# ROBO_HAND_SCH.net
KiCad netlist of a schematic drawn in Altium Designer
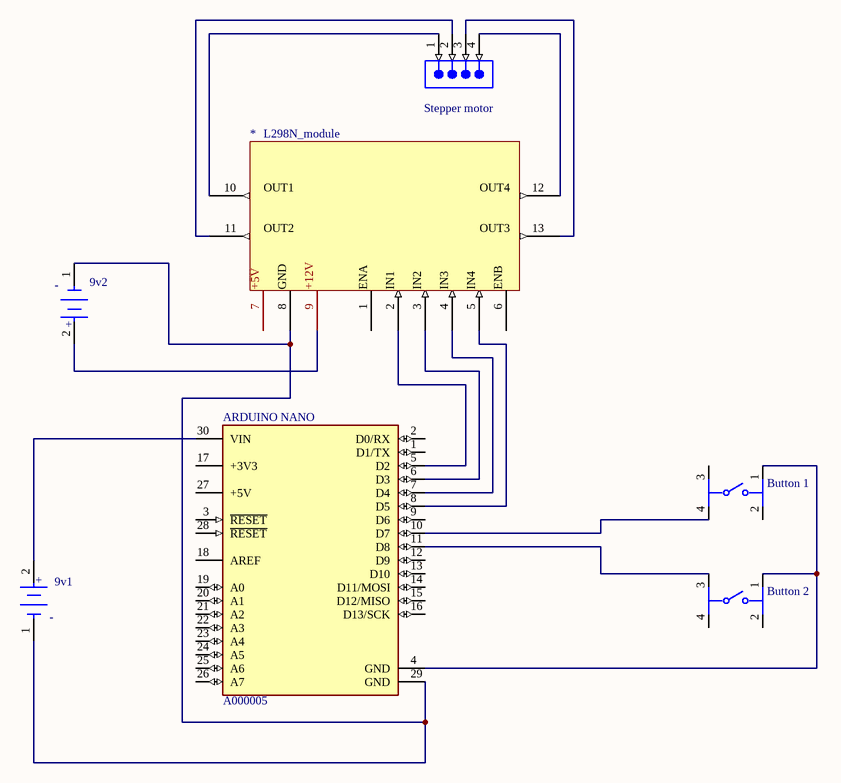
[diagram p0: ROBO HAND SCH.SchDoc]

(export (version "E")
  (design (tool "Eeschema 10.0.6"))
  (components
    (comp (ref "*") (value "L298N_module") (libsource (lib "L298N_module") (part "L298N_module")))
    (comp (ref "9v1")
      (value "BH9VPC")
      (footprint "FP-BH9VPC-MFG")
      (description "Battery Holder (Open) 9V 1 Cell PC Pin")
      (fields (field (name "OCTOPART") "https://octopart.com/bh9vpc-memory+protection+devices-22788154"))
      (libsource (lib "Altium Content Vault") (part "60d3b5b901a8747834971d0eb8cf3fd"))
    )
    (comp (ref "9v2")
      (value "BH9VPC")
      (footprint "FP-BH9VPC-MFG")
      (description "Battery Holder (Open) 9V 1 Cell PC Pin")
      (fields (field (name "OCTOPART") "https://octopart.com/bh9vpc-memory+protection+devices-22788154"))
      (libsource (lib "Altium Content Vault") (part "60d3b5b901a8747834971d0eb8cf3fd"))
    )
    (comp (ref "ARDUINO NANO")
      (value "A000005")
      (footprint "FP-A000005-MFG")
      (description "ARDUINO NANO ATMEGA328 EVAL BRD")
      (libsource (lib "Altium Content Vault") (part "d190c066e99afd1c6882cf92e11b2cc"))
    )
    (comp (ref "Button 1")
      (value "PTS645SM43SMTR92LFS")
      (footprint "FP-PTS645SM43SMTR92LFS-MFG")
      (description "SWITCH TACTILE SPST-NO 0.05A 12V")
      (libsource (lib "Altium Content Vault") (part "1adf0dd01260c80cf25a44bfd6b99ba"))
    )
    (comp (ref "Button 2")
      (value "PTS645SM43SMTR92LFS")
      (footprint "FP-PTS645SM43SMTR92LFS-MFG")
      (description "SWITCH TACTILE SPST-NO 0.05A 12V")
      (libsource (lib "Altium Content Vault") (part "1adf0dd01260c80cf25a44bfd6b99ba"))
    )
    (comp (ref "Stepper motor")
      (value "TSM-104-01-L-SH")
      (footprint "SMTC-TSM-104-01-X-SH")
      (fields (field (name "MANUFACTURER") "Samtec"))
      (libsource (lib "Altium Content Vault") (part "SMTC-TSM-104-01-X-SH"))
    )
  )
  (nets
    (net (code "1") (name "Net-(*-+12V)") (class "Default")
      (node (ref "*") (pin "9") (pinfunction "+12V_9") (pintype "power_in"))
      (node (ref "9v2") (pin "2") (pinfunction "A_2") (pintype "passive"))
    )
    (net (code "2") (name "Net-(*-GND)") (class "Default")
      (node (ref "*") (pin "8") (pinfunction "GND_8") (pintype "power_in"))
      (node (ref "9v1") (pin "1") (pinfunction "C_1") (pintype "passive"))
      (node (ref "9v2") (pin "1") (pinfunction "C_1") (pintype "passive"))
      (node (ref "ARDUINO NANO") (pin "29") (pinfunction "GND_29") (pintype "power_in"))
    )
    (net (code "3") (name "Net-(*-IN1)") (class "Default")
      (node (ref "*") (pin "2") (pinfunction "IN1_2") (pintype "input"))
      (node (ref "ARDUINO NANO") (pin "5") (pinfunction "D2_5") (pintype "bidirectional"))
    )
    (net (code "4") (name "Net-(*-IN2)") (class "Default")
      (node (ref "*") (pin "3") (pinfunction "IN2_3") (pintype "input"))
      (node (ref "ARDUINO NANO") (pin "6") (pinfunction "D3_6") (pintype "bidirectional"))
    )
    (net (code "5") (name "Net-(*-IN3)") (class "Default")
      (node (ref "*") (pin "4") (pinfunction "IN3_4") (pintype "input"))
      (node (ref "ARDUINO NANO") (pin "7") (pinfunction "D4_7") (pintype "bidirectional"))
    )
    (net (code "6") (name "Net-(*-IN4)") (class "Default")
      (node (ref "*") (pin "5") (pinfunction "IN4_5") (pintype "input"))
      (node (ref "ARDUINO NANO") (pin "8") (pinfunction "D5_8") (pintype "bidirectional"))
    )
    (net (code "7") (name "Net-(*-OUT1)") (class "Default")
      (node (ref "*") (pin "10") (pinfunction "OUT1_10") (pintype "output"))
      (node (ref "Stepper motor") (pin "1") (pinfunction "A+_1") (pintype "input"))
    )
    (net (code "8") (name "Net-(*-OUT2)") (class "Default")
      (node (ref "*") (pin "11") (pinfunction "OUT2_11") (pintype "output"))
      (node (ref "Stepper motor") (pin "2") (pinfunction "A-_2") (pintype "input"))
    )
    (net (code "9") (name "Net-(*-OUT3)") (class "Default")
      (node (ref "*") (pin "13") (pinfunction "OUT3_13") (pintype "output"))
      (node (ref "Stepper motor") (pin "3") (pinfunction "B+_3") (pintype "input"))
    )
    (net (code "10") (name "Net-(*-OUT4)") (class "Default")
      (node (ref "*") (pin "12") (pinfunction "OUT4_12") (pintype "output"))
      (node (ref "Stepper motor") (pin "4") (pinfunction "B-_4") (pintype "input"))
    )
    (net (code "11") (name "Net-(9v1-A)") (class "Default")
      (node (ref "9v1") (pin "2") (pinfunction "A_2") (pintype "passive"))
      (node (ref "ARDUINO NANO") (pin "30") (pinfunction "VIN_30") (pintype "power_in"))
    )
    (net (code "12") (name "Net-(ARDUINO NANO-D7)") (class "Default")
      (node (ref "ARDUINO NANO") (pin "10") (pinfunction "D7_10") (pintype "bidirectional"))
      (node (ref "Button 1") (pin "4") (pinfunction "4_4") (pintype "passive"))
    )
    (net (code "13") (name "Net-(ARDUINO NANO-D8)") (class "Default")
      (node (ref "ARDUINO NANO") (pin "11") (pinfunction "D8_11") (pintype "bidirectional"))
      (node (ref "Button 2") (pin "3") (pinfunction "3_3") (pintype "passive"))
    )
    (net (code "14") (name "Net-(ARDUINO NANO-GND-Pad4)") (class "Default")
      (node (ref "ARDUINO NANO") (pin "4") (pinfunction "GND_4") (pintype "power_in"))
      (node (ref "Button 1") (pin "1") (pinfunction "1_1") (pintype "passive"))
      (node (ref "Button 2") (pin "1") (pinfunction "1_1") (pintype "passive"))
    )
    (net (code "15") (name "unconnected-(*-+5V-Pad7)") (class "Default")
      (node (ref "*") (pin "7") (pinfunction "+5V_7") (pintype "power_in"))
    )
    (net (code "16") (name "unconnected-(*-ENA-Pad1)") (class "Default")
      (node (ref "*") (pin "1") (pinfunction "ENA_1") (pintype "passive"))
    )
    (net (code "17") (name "unconnected-(*-ENB-Pad6)") (class "Default")
      (node (ref "*") (pin "6") (pinfunction "ENB_6") (pintype "passive"))
    )
    (net (code "18") (name "unconnected-(ARDUINO NANO-+3V3-Pad17)") (class "Default")
      (node (ref "ARDUINO NANO") (pin "17") (pinfunction "+3V3_17") (pintype "power_in"))
    )
    (net (code "19") (name "unconnected-(ARDUINO NANO-+5V-Pad27)") (class "Default")
      (node (ref "ARDUINO NANO") (pin "27") (pinfunction "+5V_27") (pintype "power_in"))
    )
    (net (code "20") (name "unconnected-(ARDUINO NANO-A0-Pad19)") (class "Default")
      (node (ref "ARDUINO NANO") (pin "19") (pinfunction "A0_19") (pintype "bidirectional"))
    )
    (net (code "21") (name "unconnected-(ARDUINO NANO-A1-Pad20)") (class "Default")
      (node (ref "ARDUINO NANO") (pin "20") (pinfunction "A1_20") (pintype "bidirectional"))
    )
    (net (code "22") (name "unconnected-(ARDUINO NANO-A2-Pad21)") (class "Default")
      (node (ref "ARDUINO NANO") (pin "21") (pinfunction "A2_21") (pintype "bidirectional"))
    )
    (net (code "23") (name "unconnected-(ARDUINO NANO-A3-Pad22)") (class "Default")
      (node (ref "ARDUINO NANO") (pin "22") (pinfunction "A3_22") (pintype "bidirectional"))
    )
    (net (code "24") (name "unconnected-(ARDUINO NANO-A4-Pad23)") (class "Default")
      (node (ref "ARDUINO NANO") (pin "23") (pinfunction "A4_23") (pintype "bidirectional"))
    )
    (net (code "25") (name "unconnected-(ARDUINO NANO-A5-Pad24)") (class "Default")
      (node (ref "ARDUINO NANO") (pin "24") (pinfunction "A5_24") (pintype "bidirectional"))
    )
    (net (code "26") (name "unconnected-(ARDUINO NANO-A6-Pad25)") (class "Default")
      (node (ref "ARDUINO NANO") (pin "25") (pinfunction "A6_25") (pintype "bidirectional"))
    )
    (net (code "27") (name "unconnected-(ARDUINO NANO-A7-Pad26)") (class "Default")
      (node (ref "ARDUINO NANO") (pin "26") (pinfunction "A7_26") (pintype "bidirectional"))
    )
    (net (code "28") (name "unconnected-(ARDUINO NANO-AREF-Pad18)") (class "Default")
      (node (ref "ARDUINO NANO") (pin "18") (pinfunction "AREF_18") (pintype "passive"))
    )
    (net (code "29") (name "unconnected-(ARDUINO NANO-D0{slash}RX-Pad2)") (class "Default")
      (node (ref "ARDUINO NANO") (pin "2") (pinfunction "D0/RX_2") (pintype "bidirectional"))
    )
    (net (code "30") (name "unconnected-(ARDUINO NANO-D1{slash}TX-Pad1)") (class "Default")
      (node (ref "ARDUINO NANO") (pin "1") (pinfunction "D1/TX_1") (pintype "bidirectional"))
    )
    (net (code "31") (name "unconnected-(ARDUINO NANO-D6-Pad9)") (class "Default")
      (node (ref "ARDUINO NANO") (pin "9") (pinfunction "D6_9") (pintype "bidirectional"))
    )
    (net (code "32") (name "unconnected-(ARDUINO NANO-D9-Pad12)") (class "Default")
      (node (ref "ARDUINO NANO") (pin "12") (pinfunction "D9_12") (pintype "bidirectional"))
    )
    (net (code "33") (name "unconnected-(ARDUINO NANO-D10-Pad13)") (class "Default")
      (node (ref "ARDUINO NANO") (pin "13") (pinfunction "D10_13") (pintype "bidirectional"))
    )
    (net (code "34") (name "unconnected-(ARDUINO NANO-D11{slash}MOSI-Pad14)") (class "Default")
      (node (ref "ARDUINO NANO") (pin "14") (pinfunction "D11/MOSI_14") (pintype "bidirectional"))
    )
    (net (code "35") (name "unconnected-(ARDUINO NANO-D12{slash}MISO-Pad15)") (class "Default")
      (node (ref "ARDUINO NANO") (pin "15") (pinfunction "D12/MISO_15") (pintype "bidirectional"))
    )
    (net (code "36") (name "unconnected-(ARDUINO NANO-D13{slash}SCK-Pad16)") (class "Default")
      (node (ref "ARDUINO NANO") (pin "16") (pinfunction "D13/SCK_16") (pintype "bidirectional"))
    )
    (net (code "37") (name "unconnected-(ARDUINO NANO-~{RESET}-Pad3)") (class "Default")
      (node (ref "ARDUINO NANO") (pin "3") (pinfunction "~{RESET}_3") (pintype "input"))
    )
    (net (code "38") (name "unconnected-(ARDUINO NANO-~{RESET}-Pad28)") (class "Default")
      (node (ref "ARDUINO NANO") (pin "28") (pinfunction "~{RESET}_28") (pintype "input"))
    )
    (net (code "39") (name "unconnected-(Button 1-Pad2)") (class "Default")
      (node (ref "Button 1") (pin "2") (pinfunction "2_2") (pintype "passive"))
    )
    (net (code "40") (name "unconnected-(Button 1-Pad3)") (class "Default")
      (node (ref "Button 1") (pin "3") (pinfunction "3_3") (pintype "passive"))
    )
    (net (code "41") (name "unconnected-(Button 2-Pad2)") (class "Default")
      (node (ref "Button 2") (pin "2") (pinfunction "2_2") (pintype "passive"))
    )
    (net (code "42") (name "unconnected-(Button 2-Pad4)") (class "Default")
      (node (ref "Button 2") (pin "4") (pinfunction "4_4") (pintype "passive"))
    )
  )
)
